# NVME.net
KiCad netlist of a schematic drawn in Altium Designer
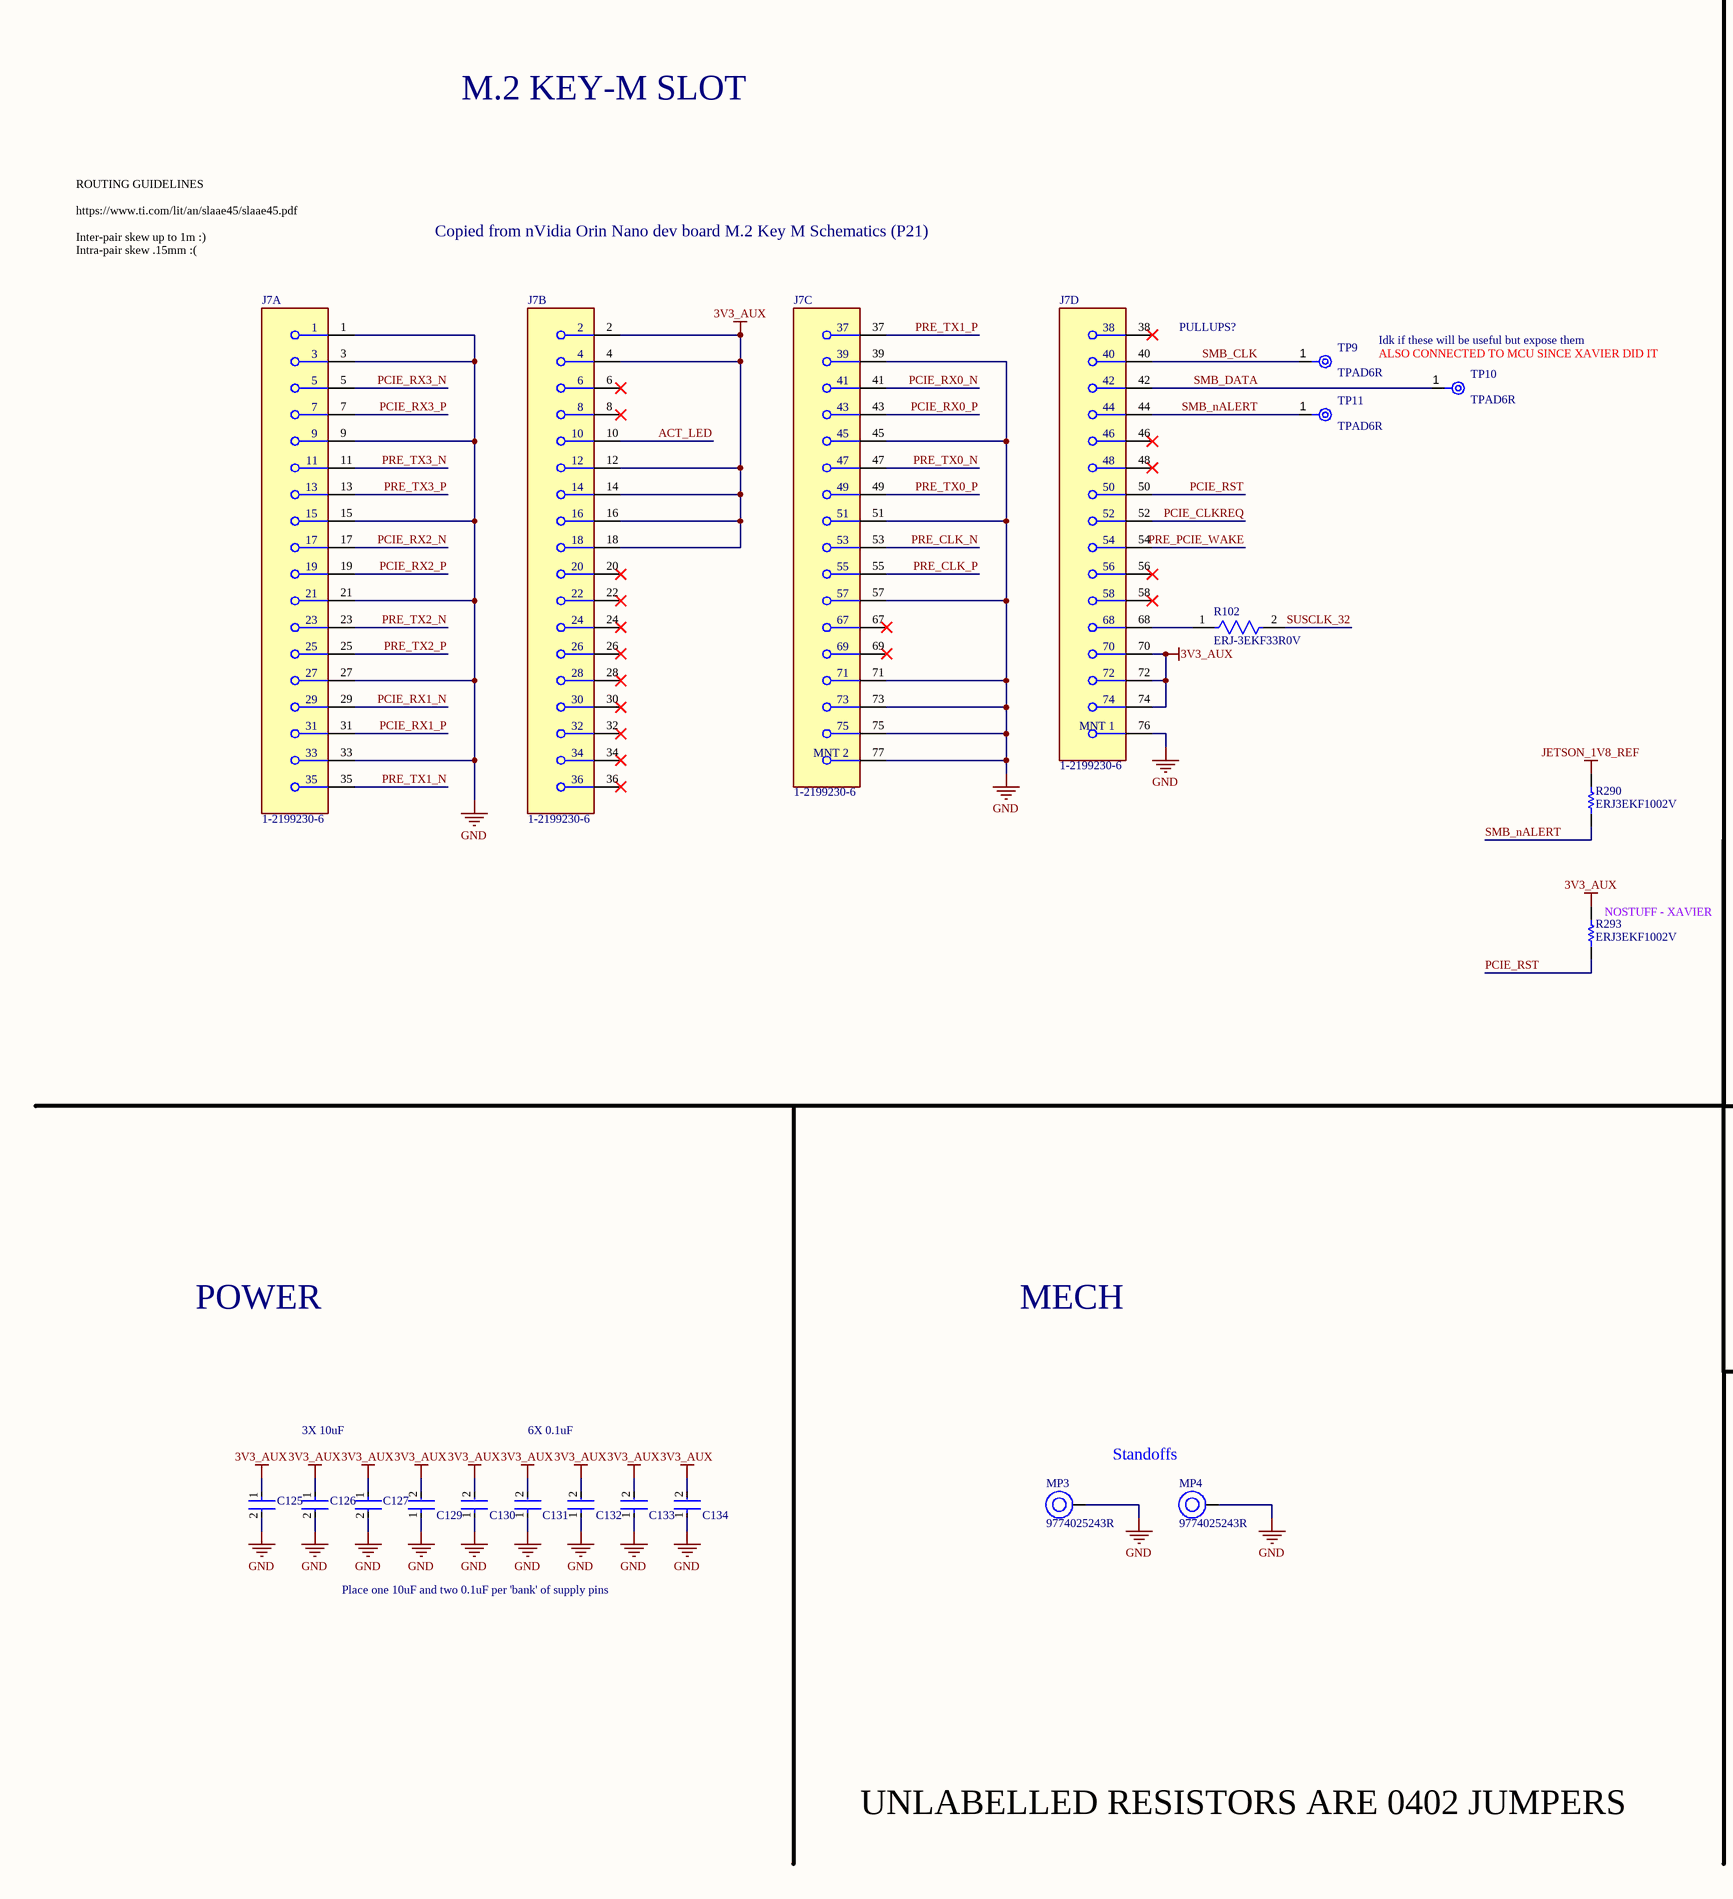
[diagram p0: NVME.SchDoc, left]
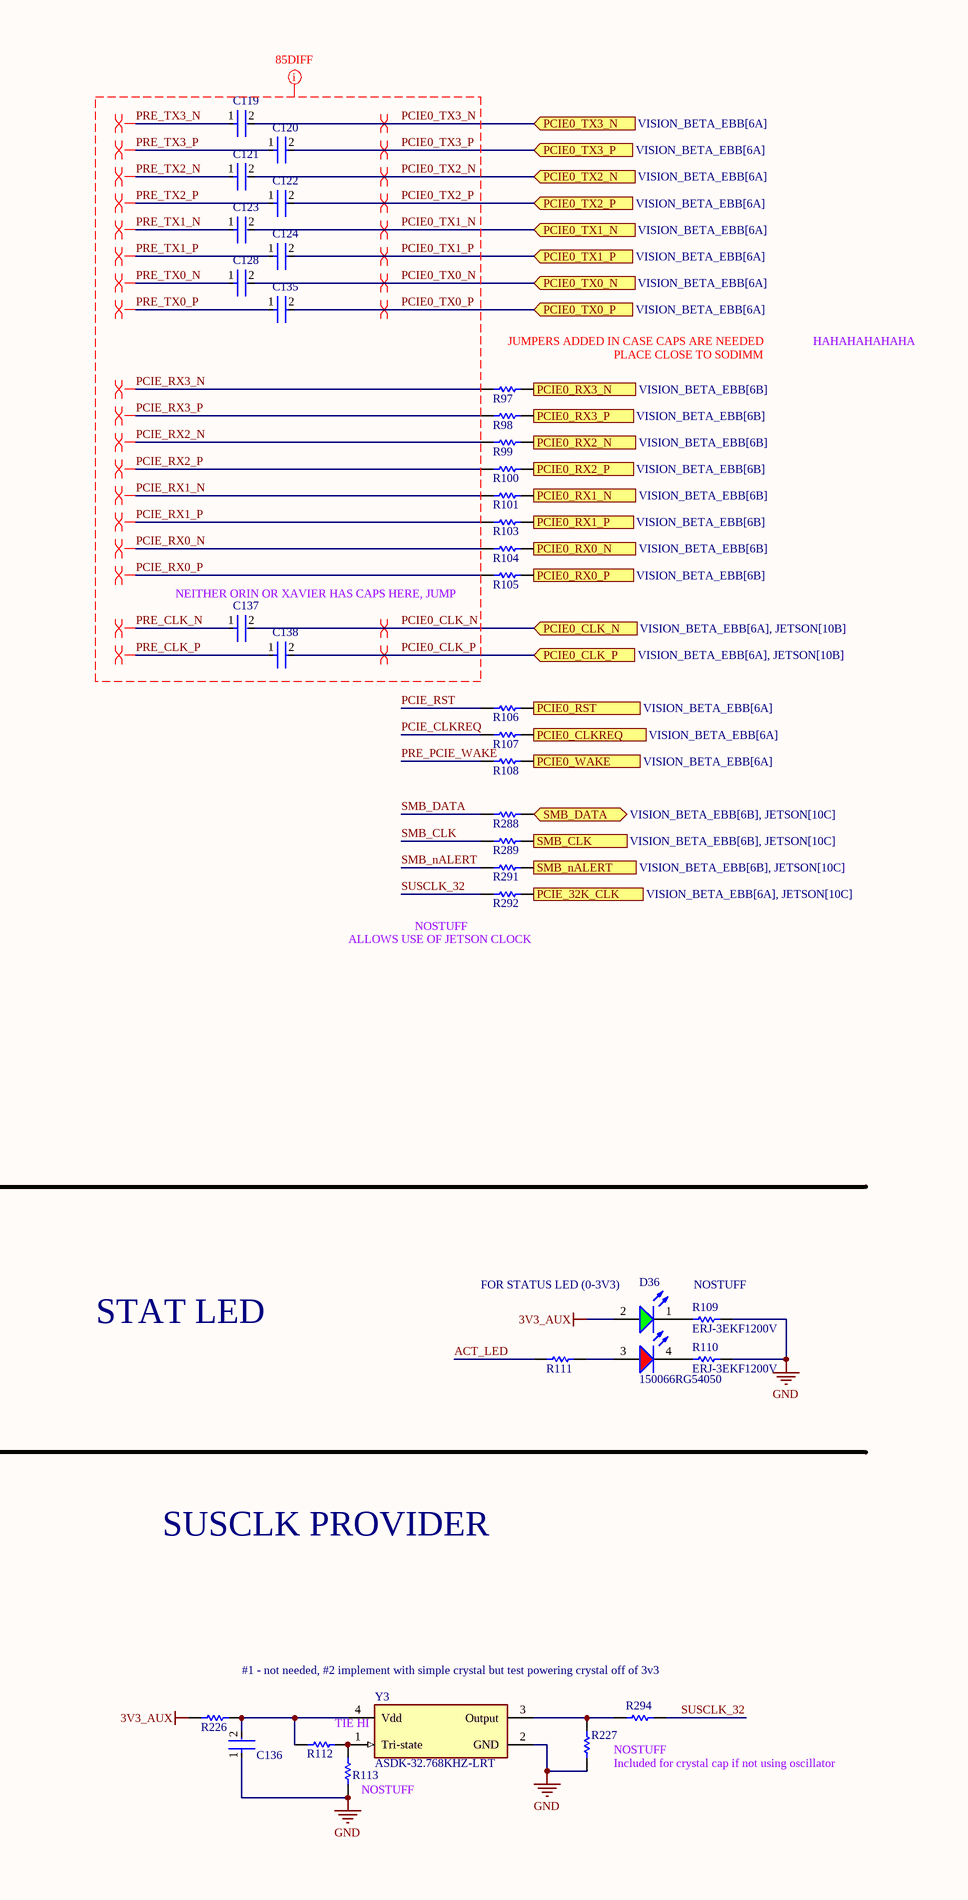
[diagram p1: NVME.SchDoc, right]

(export (version "E")
  (design (tool "Eeschema 10.0.6"))
  (components
    (comp (ref "C119")
      (value "C1005X7R1A224K050BB")
      (footprint "FP-C1005-050-0_05-IPC_C")
      (description "Multilayer Ceramic Capacitors 220nF ±10% 10V X7R SMD 0402")
      (fields (field (name "TOLERANCE") "10%"))
      (libsource (lib "Altium Content Vault") (part "b4654b650e69147ec39a6b967a45e02"))
    )
    (comp (ref "C120")
      (value "C1005X7R1A224K050BB")
      (footprint "FP-C1005-050-0_05-IPC_C")
      (description "Multilayer Ceramic Capacitors 220nF ±10% 10V X7R SMD 0402")
      (fields (field (name "TOLERANCE") "10%"))
      (libsource (lib "Altium Content Vault") (part "b4654b650e69147ec39a6b967a45e02"))
    )
    (comp (ref "C121")
      (value "C1005X7R1A224K050BB")
      (footprint "FP-C1005-050-0_05-IPC_C")
      (description "Multilayer Ceramic Capacitors 220nF ±10% 10V X7R SMD 0402")
      (fields (field (name "TOLERANCE") "10%"))
      (libsource (lib "Altium Content Vault") (part "b4654b650e69147ec39a6b967a45e02"))
    )
    (comp (ref "C122")
      (value "C1005X7R1A224K050BB")
      (footprint "FP-C1005-050-0_05-IPC_C")
      (description "Multilayer Ceramic Capacitors 220nF ±10% 10V X7R SMD 0402")
      (fields (field (name "TOLERANCE") "10%"))
      (libsource (lib "Altium Content Vault") (part "b4654b650e69147ec39a6b967a45e02"))
    )
    (comp (ref "C123")
      (value "C1005X7R1A224K050BB")
      (footprint "FP-C1005-050-0_05-IPC_C")
      (description "Multilayer Ceramic Capacitors 220nF ±10% 10V X7R SMD 0402")
      (fields (field (name "TOLERANCE") "10%"))
      (libsource (lib "Altium Content Vault") (part "b4654b650e69147ec39a6b967a45e02"))
    )
    (comp (ref "C124")
      (value "C1005X7R1A224K050BB")
      (footprint "FP-C1005-050-0_05-IPC_C")
      (description "Multilayer Ceramic Capacitors 220nF ±10% 10V X7R SMD 0402")
      (fields (field (name "TOLERANCE") "10%"))
      (libsource (lib "Altium Content Vault") (part "b4654b650e69147ec39a6b967a45e02"))
    )
    (comp (ref "C125")
      (value "GRM188R60J106ME47D")
      (footprint "FP-GRM188-0_1-e0_2_0_55-IPC_A")
      (description "Chip Multilayer Ceramic Capacitors for General Purpose, 0603, 10uF, X5R, 15%, 20%, 6.3V")
      (fields (field (name "VOLTAGE") "6.3V") (field (name "TOLERANCE") "20%"))
      (libsource (lib "Altium Content Vault") (part "02cd4be3c70576c341d710602a673aa"))
    )
    (comp (ref "C126")
      (value "GRM188R60J106ME47D")
      (footprint "FP-GRM188-0_1-e0_2_0_55-IPC_A")
      (description "Chip Multilayer Ceramic Capacitors for General Purpose, 0603, 10uF, X5R, 15%, 20%, 6.3V")
      (fields (field (name "VOLTAGE") "6.3V") (field (name "TOLERANCE") "20%"))
      (libsource (lib "Altium Content Vault") (part "02cd4be3c70576c341d710602a673aa"))
    )
    (comp (ref "C127")
      (value "GRM188R60J106ME47D")
      (footprint "FP-GRM188-0_1-e0_2_0_55-IPC_A")
      (description "Chip Multilayer Ceramic Capacitors for General Purpose, 0603, 10uF, X5R, 15%, 20%, 6.3V")
      (fields (field (name "VOLTAGE") "6.3V") (field (name "TOLERANCE") "20%"))
      (libsource (lib "Altium Content Vault") (part "02cd4be3c70576c341d710602a673aa"))
    )
    (comp (ref "C128")
      (value "C1005X7R1A224K050BB")
      (footprint "FP-C1005-050-0_05-IPC_C")
      (description "Multilayer Ceramic Capacitors 220nF ±10% 10V X7R SMD 0402")
      (fields (field (name "TOLERANCE") "10%"))
      (libsource (lib "Altium Content Vault") (part "b4654b650e69147ec39a6b967a45e02"))
    )
    (comp (ref "C129")
      (value "C1005X7R1H104K050BB")
      (footprint "FP-C1005-050-0_05-IPC_C")
      (description "Multilayer Ceramic Capacitors 100nF ±10% 50V X7R SMD 0402")
      (fields (field (name "VOLTAGE") "50V") (field (name "TOLERANCE") "10%"))
      (libsource (lib "Altium Content Vault") (part "b4654b650e69147ec39a6b967a45e02"))
    )
    (comp (ref "C130")
      (value "C1005X7R1H104K050BB")
      (footprint "FP-C1005-050-0_05-IPC_C")
      (description "Multilayer Ceramic Capacitors 100nF ±10% 50V X7R SMD 0402")
      (fields (field (name "VOLTAGE") "50V") (field (name "TOLERANCE") "10%"))
      (libsource (lib "Altium Content Vault") (part "b4654b650e69147ec39a6b967a45e02"))
    )
    (comp (ref "C131")
      (value "C1005X7R1H104K050BB")
      (footprint "FP-C1005-050-0_05-IPC_C")
      (description "Multilayer Ceramic Capacitors 100nF ±10% 50V X7R SMD 0402")
      (fields (field (name "VOLTAGE") "50V") (field (name "TOLERANCE") "10%"))
      (libsource (lib "Altium Content Vault") (part "b4654b650e69147ec39a6b967a45e02"))
    )
    (comp (ref "C132")
      (value "C1005X7R1H104K050BB")
      (footprint "FP-C1005-050-0_05-IPC_C")
      (description "Multilayer Ceramic Capacitors 100nF ±10% 50V X7R SMD 0402")
      (fields (field (name "VOLTAGE") "50V") (field (name "TOLERANCE") "10%"))
      (libsource (lib "Altium Content Vault") (part "b4654b650e69147ec39a6b967a45e02"))
    )
    (comp (ref "C133")
      (value "C1005X7R1H104K050BB")
      (footprint "FP-C1005-050-0_05-IPC_C")
      (description "Multilayer Ceramic Capacitors 100nF ±10% 50V X7R SMD 0402")
      (fields (field (name "VOLTAGE") "50V") (field (name "TOLERANCE") "10%"))
      (libsource (lib "Altium Content Vault") (part "b4654b650e69147ec39a6b967a45e02"))
    )
    (comp (ref "C134")
      (value "C1005X7R1H104K050BB")
      (footprint "FP-C1005-050-0_05-IPC_C")
      (description "Multilayer Ceramic Capacitors 100nF ±10% 50V X7R SMD 0402")
      (fields (field (name "VOLTAGE") "50V") (field (name "TOLERANCE") "10%"))
      (libsource (lib "Altium Content Vault") (part "b4654b650e69147ec39a6b967a45e02"))
    )
    (comp (ref "C135")
      (value "C1005X7R1A224K050BB")
      (footprint "FP-C1005-050-0_05-IPC_C")
      (description "Multilayer Ceramic Capacitors 220nF ±10% 10V X7R SMD 0402")
      (fields (field (name "TOLERANCE") "10%"))
      (libsource (lib "Altium Content Vault") (part "b4654b650e69147ec39a6b967a45e02"))
    )
    (comp (ref "C136")
      (value "C1005X7R1H104K050BB")
      (footprint "FP-C1005-050-0_05-IPC_C")
      (description "Multilayer Ceramic Capacitors 100nF ±10% 50V X7R SMD 0402")
      (fields (field (name "VOLTAGE") "50V") (field (name "TOLERANCE") "10%"))
      (libsource (lib "Altium Content Vault") (part "b4654b650e69147ec39a6b967a45e02"))
    )
    (comp (ref "C137")
      (value "C1005X7R1A224K050BB")
      (footprint "FP-C1005-050-0_05-IPC_C")
      (description "Multilayer Ceramic Capacitors 220nF ±10% 10V X7R SMD 0402")
      (fields (field (name "TOLERANCE") "10%"))
      (libsource (lib "Altium Content Vault") (part "b4654b650e69147ec39a6b967a45e02"))
    )
    (comp (ref "C138")
      (value "C1005X7R1A224K050BB")
      (footprint "FP-C1005-050-0_05-IPC_C")
      (description "Multilayer Ceramic Capacitors 220nF ±10% 10V X7R SMD 0402")
      (fields (field (name "TOLERANCE") "10%"))
      (libsource (lib "Altium Content Vault") (part "b4654b650e69147ec39a6b967a45e02"))
    )
    (comp (ref "D36")
      (value "150066RG54050")
      (footprint "WL-SBCD_0606")
      (description "Led, Red/Grn, 180Mcd/230Mcd, 624Nm/525Nm Rohs Compliant: Yes")
      (fields (field (name "SOURCE") "rgled.SchLib"))
      (libsource (lib "Space Concordia") (part "CMP-004-00034-2"))
    )
    (comp (ref "J7")
      (value "1-2199230-6")
      (footprint "FP-1-2199230-6-MFG")
      (description "CONN EDGE DUAL FMALE 67POS 0.020")
      (fields
        (field (name "MANUFACTURER") "TE")
        (field (name "OCTOPART") "https://octopart.com/1-2199230-6-te+connectivity-34969376")
      )
      (libsource (lib "Altium Content Vault") (part "bdc5cd39fb5e3adfc3cf7d042564072"))
    )
    (comp (ref "MP3")
      (value "9774025243R")
      (footprint "9774025243")
      (description "9774025243R Spacer Material: Steel, Tin-Plated Mounting: SMT Series: WA-SMST Thread D: M2")
      (libsource (lib "Altium Content Vault") (part "Spacer"))
    )
    (comp (ref "MP4")
      (value "9774025243R")
      (footprint "9774025243")
      (description "9774025243R Spacer Material: Steel, Tin-Plated Mounting: SMT Series: WA-SMST Thread D: M2")
      (libsource (lib "Altium Content Vault") (part "Spacer"))
    )
    (comp (ref "R97")
      (value "0402 JUMPER")
      (footprint "RESC1005X40X25ML05T05")
      (description "READ THE NAME")
      (libsource (lib "Space Concordia") (part "CMP-009-00206-2"))
    )
    (comp (ref "R98")
      (value "0402 JUMPER")
      (footprint "RESC1005X40X25ML05T05")
      (description "READ THE NAME")
      (libsource (lib "Space Concordia") (part "CMP-009-00206-2"))
    )
    (comp (ref "R99")
      (value "0402 JUMPER")
      (footprint "RESC1005X40X25ML05T05")
      (description "READ THE NAME")
      (libsource (lib "Space Concordia") (part "CMP-009-00206-2"))
    )
    (comp (ref "R100")
      (value "0402 JUMPER")
      (footprint "RESC1005X40X25ML05T05")
      (description "READ THE NAME")
      (libsource (lib "Space Concordia") (part "CMP-009-00206-2"))
    )
    (comp (ref "R101")
      (value "0402 JUMPER")
      (footprint "RESC1005X40X25ML05T05")
      (description "READ THE NAME")
      (libsource (lib "Space Concordia") (part "CMP-009-00206-2"))
    )
    (comp (ref "R102")
      (value "ERJ-3EKF33R0V")
      (footprint "FP-ERJ3EK-MFG")
      (description "RES SMD 33 OHM 1% 1/10W 0603")
      (fields (field (name "TOLERANCE") "1%"))
      (libsource (lib "Altium Content Vault") (part "1029c3af85768c4190bb7ad29bc67b5"))
    )
    (comp (ref "R103")
      (value "0402 JUMPER")
      (footprint "RESC1005X40X25ML05T05")
      (description "READ THE NAME")
      (libsource (lib "Space Concordia") (part "CMP-009-00206-2"))
    )
    (comp (ref "R104")
      (value "0402 JUMPER")
      (footprint "RESC1005X40X25ML05T05")
      (description "READ THE NAME")
      (libsource (lib "Space Concordia") (part "CMP-009-00206-2"))
    )
    (comp (ref "R105")
      (value "0402 JUMPER")
      (footprint "RESC1005X40X25ML05T05")
      (description "READ THE NAME")
      (libsource (lib "Space Concordia") (part "CMP-009-00206-2"))
    )
    (comp (ref "R106")
      (value "0402 JUMPER")
      (footprint "RESC1005X40X25ML05T05")
      (description "READ THE NAME")
      (libsource (lib "Space Concordia") (part "CMP-009-00206-2"))
    )
    (comp (ref "R107")
      (value "0402 JUMPER")
      (footprint "RESC1005X40X25ML05T05")
      (description "READ THE NAME")
      (libsource (lib "Space Concordia") (part "CMP-009-00206-2"))
    )
    (comp (ref "R108")
      (value "0402 JUMPER")
      (footprint "RESC1005X40X25ML05T05")
      (description "READ THE NAME")
      (libsource (lib "Space Concordia") (part "CMP-009-00206-2"))
    )
    (comp (ref "R109")
      (value "ERJ-3EKF1200V")
      (footprint "RESC1609X55X30ML15T15")
      (description "Chip Resistor, 120 Ohm, +/- 1%, 0.1 W, -55 to 155 degC, 0603 (1608 Metric), RoHS, Tape and Reel")
      (fields (field (name "TOLERANCE") "1%") (field (name "MANUFACTURER") "Panasonic"))
      (libsource (lib "Altium Content Vault") (part "RES-2"))
    )
    (comp (ref "R110")
      (value "ERJ-3EKF1200V")
      (footprint "RESC1609X55X30ML15T15")
      (description "Chip Resistor, 120 Ohm, +/- 1%, 0.1 W, -55 to 155 degC, 0603 (1608 Metric), RoHS, Tape and Reel")
      (fields (field (name "TOLERANCE") "1%") (field (name "MANUFACTURER") "Panasonic"))
      (libsource (lib "Altium Content Vault") (part "RES-2"))
    )
    (comp (ref "R111")
      (value "0402 JUMPER")
      (footprint "RESC1005X40X25ML05T05")
      (description "READ THE NAME")
      (libsource (lib "Space Concordia") (part "CMP-009-00206-2"))
    )
    (comp (ref "R112")
      (value "0402 JUMPER")
      (footprint "RESC1005X40X25ML05T05")
      (description "READ THE NAME")
      (libsource (lib "Space Concordia") (part "CMP-009-00206-2"))
    )
    (comp (ref "R113")
      (value "0402 JUMPER")
      (footprint "RESC1005X40X25ML05T05")
      (description "READ THE NAME")
      (libsource (lib "Space Concordia") (part "CMP-009-00206-2"))
    )
    (comp (ref "R226")
      (value "0402 JUMPER")
      (footprint "RESC1005X40X25ML05T05")
      (description "READ THE NAME")
      (libsource (lib "Space Concordia") (part "CMP-009-00206-2"))
    )
    (comp (ref "R227")
      (value "0402 JUMPER")
      (footprint "RESC1005X40X25ML05T05")
      (description "READ THE NAME")
      (libsource (lib "Space Concordia") (part "CMP-009-00206-2"))
    )
    (comp (ref "R288")
      (value "0402 JUMPER")
      (footprint "RESC1005X40X25ML05T05")
      (description "READ THE NAME")
      (libsource (lib "Space Concordia") (part "CMP-009-00206-2"))
    )
    (comp (ref "R289")
      (value "0402 JUMPER")
      (footprint "RESC1005X40X25ML05T05")
      (description "READ THE NAME")
      (libsource (lib "Space Concordia") (part "CMP-009-00206-2"))
    )
    (comp (ref "R290")
      (value "ERJ3EKF1002V")
      (footprint "RESC1609X55X30LL15T15")
      (description "Chip Resistor, 10 KOhm, +/- 1%, 0.1 W, -55 to 155 degC, 0603 (1608 Metric), RoHS, Tape and Reel")
      (fields (field (name "TOLERANCE") "1%") (field (name "MANUFACTURER") "Panasonic"))
      (libsource (lib "Altium Content Vault") (part "RES-2"))
    )
    (comp (ref "R291")
      (value "0402 JUMPER")
      (footprint "RESC1005X40X25ML05T05")
      (description "READ THE NAME")
      (libsource (lib "Space Concordia") (part "CMP-009-00206-2"))
    )
    (comp (ref "R292")
      (value "0402 JUMPER")
      (footprint "RESC1005X40X25ML05T05")
      (description "READ THE NAME")
      (libsource (lib "Space Concordia") (part "CMP-009-00206-2"))
    )
    (comp (ref "R293")
      (value "ERJ3EKF1002V")
      (footprint "RESC1609X55X30LL15T15")
      (description "Chip Resistor, 10 KOhm, +/- 1%, 0.1 W, -55 to 155 degC, 0603 (1608 Metric), RoHS, Tape and Reel")
      (fields (field (name "TOLERANCE") "1%") (field (name "MANUFACTURER") "Panasonic"))
      (libsource (lib "Altium Content Vault") (part "RES-2"))
    )
    (comp (ref "R294")
      (value "0402 JUMPER")
      (footprint "RESC1005X40X25ML05T05")
      (description "READ THE NAME")
      (libsource (lib "Space Concordia") (part "CMP-009-00206-2"))
    )
    (comp (ref "TP9")
      (value "TPAD6R")
      (footprint "New footprint 1")
      (description "Test Point .6mm")
      (libsource (lib "Space Concordia") (part "TP"))
    )
    (comp (ref "TP10")
      (value "TPAD6R")
      (footprint "New footprint 1")
      (description "Test Point .6mm")
      (libsource (lib "Space Concordia") (part "TP"))
    )
    (comp (ref "TP11")
      (value "TPAD6R")
      (footprint "New footprint 1")
      (description "Test Point .6mm")
      (libsource (lib "Space Concordia") (part "TP"))
    )
    (comp (ref "Y3")
      (value "ASDK-32.768KHZ-LRT")
      (footprint "FP-ASDK-MFG")
      (description "XTAL OSC XO 32.7680KHZ CMOS SMD")
      (libsource (lib "Altium Content Vault") (part "a7425352bb6ebc83bfd0f12a23808e7"))
    )
  )
  (nets
    (net (code "1") (name "/ACT_LED") (class "Default")
      (node (ref "J7") (pin "10") (pinfunction "10_10") (pintype "passive"))
      (node (ref "R111") (pin "1") (pinfunction "1_1") (pintype "passive"))
    )
    (net (code "2") (name "/PCIE0_CLKREQ") (class "Default")
      (node (ref "R107") (pin "2") (pinfunction "2_2") (pintype "passive"))
    )
    (net (code "3") (name "/PCIE0_CLK_N") (class "Default")
      (node (ref "C137") (pin "2") (pinfunction "2_2") (pintype "passive"))
    )
    (net (code "4") (name "/PCIE0_CLK_P") (class "Default")
      (node (ref "C138") (pin "2") (pinfunction "2_2") (pintype "passive"))
    )
    (net (code "5") (name "/PCIE0_RST") (class "Default")
      (node (ref "R106") (pin "2") (pinfunction "2_2") (pintype "passive"))
    )
    (net (code "6") (name "/PCIE0_RX0_N") (class "Default")
      (node (ref "R104") (pin "2") (pinfunction "2_2") (pintype "passive"))
    )
    (net (code "7") (name "/PCIE0_RX0_P") (class "Default")
      (node (ref "R105") (pin "2") (pinfunction "2_2") (pintype "passive"))
    )
    (net (code "8") (name "/PCIE0_RX1_N") (class "Default")
      (node (ref "R101") (pin "2") (pinfunction "2_2") (pintype "passive"))
    )
    (net (code "9") (name "/PCIE0_RX1_P") (class "Default")
      (node (ref "R103") (pin "2") (pinfunction "2_2") (pintype "passive"))
    )
    (net (code "10") (name "/PCIE0_RX2_N") (class "Default")
      (node (ref "R99") (pin "2") (pinfunction "2_2") (pintype "passive"))
    )
    (net (code "11") (name "/PCIE0_RX2_P") (class "Default")
      (node (ref "R100") (pin "2") (pinfunction "2_2") (pintype "passive"))
    )
    (net (code "12") (name "/PCIE0_RX3_N") (class "Default")
      (node (ref "R97") (pin "2") (pinfunction "2_2") (pintype "passive"))
    )
    (net (code "13") (name "/PCIE0_RX3_P") (class "Default")
      (node (ref "R98") (pin "2") (pinfunction "2_2") (pintype "passive"))
    )
    (net (code "14") (name "/PCIE0_TX0_N") (class "Default")
      (node (ref "C128") (pin "2") (pinfunction "2_2") (pintype "passive"))
    )
    (net (code "15") (name "/PCIE0_TX0_P") (class "Default")
      (node (ref "C135") (pin "2") (pinfunction "2_2") (pintype "passive"))
    )
    (net (code "16") (name "/PCIE0_TX1_N") (class "Default")
      (node (ref "C123") (pin "2") (pinfunction "2_2") (pintype "passive"))
    )
    (net (code "17") (name "/PCIE0_TX1_P") (class "Default")
      (node (ref "C124") (pin "2") (pinfunction "2_2") (pintype "passive"))
    )
    (net (code "18") (name "/PCIE0_TX2_N") (class "Default")
      (node (ref "C121") (pin "2") (pinfunction "2_2") (pintype "passive"))
    )
    (net (code "19") (name "/PCIE0_TX2_P") (class "Default")
      (node (ref "C122") (pin "2") (pinfunction "2_2") (pintype "passive"))
    )
    (net (code "20") (name "/PCIE0_TX3_N") (class "Default")
      (node (ref "C119") (pin "2") (pinfunction "2_2") (pintype "passive"))
    )
    (net (code "21") (name "/PCIE0_TX3_P") (class "Default")
      (node (ref "C120") (pin "2") (pinfunction "2_2") (pintype "passive"))
    )
    (net (code "22") (name "/PCIE0_WAKE") (class "Default")
      (node (ref "R108") (pin "2") (pinfunction "2_2") (pintype "passive"))
    )
    (net (code "23") (name "/PCIE_32K_CLK") (class "Default")
      (node (ref "R292") (pin "2") (pinfunction "2_2") (pintype "passive"))
    )
    (net (code "24") (name "/PCIE_CLKREQ") (class "Default")
      (node (ref "J7") (pin "52") (pinfunction "52_52") (pintype "passive"))
      (node (ref "R107") (pin "1") (pinfunction "1_1") (pintype "passive"))
    )
    (net (code "25") (name "/PCIE_RST") (class "Default")
      (node (ref "J7") (pin "50") (pinfunction "50_50") (pintype "passive"))
      (node (ref "R106") (pin "1") (pinfunction "1_1") (pintype "passive"))
      (node (ref "R293") (pin "1") (pinfunction "1_1") (pintype "passive"))
    )
    (net (code "26") (name "/PCIE_RX0_N") (class "Default")
      (node (ref "J7") (pin "41") (pinfunction "41_41") (pintype "passive"))
      (node (ref "R104") (pin "1") (pinfunction "1_1") (pintype "passive"))
    )
    (net (code "27") (name "/PCIE_RX0_P") (class "Default")
      (node (ref "J7") (pin "43") (pinfunction "43_43") (pintype "passive"))
      (node (ref "R105") (pin "1") (pinfunction "1_1") (pintype "passive"))
    )
    (net (code "28") (name "/PCIE_RX1_N") (class "Default")
      (node (ref "J7") (pin "29") (pinfunction "29_29") (pintype "passive"))
      (node (ref "R101") (pin "1") (pinfunction "1_1") (pintype "passive"))
    )
    (net (code "29") (name "/PCIE_RX1_P") (class "Default")
      (node (ref "J7") (pin "31") (pinfunction "31_31") (pintype "passive"))
      (node (ref "R103") (pin "1") (pinfunction "1_1") (pintype "passive"))
    )
    (net (code "30") (name "/PCIE_RX2_N") (class "Default")
      (node (ref "J7") (pin "17") (pinfunction "17_17") (pintype "passive"))
      (node (ref "R99") (pin "1") (pinfunction "1_1") (pintype "passive"))
    )
    (net (code "31") (name "/PCIE_RX2_P") (class "Default")
      (node (ref "J7") (pin "19") (pinfunction "19_19") (pintype "passive"))
      (node (ref "R100") (pin "1") (pinfunction "1_1") (pintype "passive"))
    )
    (net (code "32") (name "/PCIE_RX3_N") (class "Default")
      (node (ref "J7") (pin "5") (pinfunction "5_5") (pintype "passive"))
      (node (ref "R97") (pin "1") (pinfunction "1_1") (pintype "passive"))
    )
    (net (code "33") (name "/PCIE_RX3_P") (class "Default")
      (node (ref "J7") (pin "7") (pinfunction "7_7") (pintype "passive"))
      (node (ref "R98") (pin "1") (pinfunction "1_1") (pintype "passive"))
    )
    (net (code "34") (name "/PRE_CLK_N") (class "Default")
      (node (ref "C137") (pin "1") (pinfunction "1_1") (pintype "passive"))
      (node (ref "J7") (pin "53") (pinfunction "53_53") (pintype "passive"))
    )
    (net (code "35") (name "/PRE_CLK_P") (class "Default")
      (node (ref "C138") (pin "1") (pinfunction "1_1") (pintype "passive"))
      (node (ref "J7") (pin "55") (pinfunction "55_55") (pintype "passive"))
    )
    (net (code "36") (name "/PRE_PCIE_WAKE") (class "Default")
      (node (ref "J7") (pin "54") (pinfunction "54_54") (pintype "passive"))
      (node (ref "R108") (pin "1") (pinfunction "1_1") (pintype "passive"))
    )
    (net (code "37") (name "/PRE_TX0_N") (class "Default")
      (node (ref "C128") (pin "1") (pinfunction "1_1") (pintype "passive"))
      (node (ref "J7") (pin "47") (pinfunction "47_47") (pintype "passive"))
    )
    (net (code "38") (name "/PRE_TX0_P") (class "Default")
      (node (ref "C135") (pin "1") (pinfunction "1_1") (pintype "passive"))
      (node (ref "J7") (pin "49") (pinfunction "49_49") (pintype "passive"))
    )
    (net (code "39") (name "/PRE_TX1_N") (class "Default")
      (node (ref "C123") (pin "1") (pinfunction "1_1") (pintype "passive"))
      (node (ref "J7") (pin "35") (pinfunction "35_35") (pintype "passive"))
    )
    (net (code "40") (name "/PRE_TX1_P") (class "Default")
      (node (ref "C124") (pin "1") (pinfunction "1_1") (pintype "passive"))
      (node (ref "J7") (pin "37") (pinfunction "37_37") (pintype "passive"))
    )
    (net (code "41") (name "/PRE_TX2_N") (class "Default")
      (node (ref "C121") (pin "1") (pinfunction "1_1") (pintype "passive"))
      (node (ref "J7") (pin "23") (pinfunction "23_23") (pintype "passive"))
    )
    (net (code "42") (name "/PRE_TX2_P") (class "Default")
      (node (ref "C122") (pin "1") (pinfunction "1_1") (pintype "passive"))
      (node (ref "J7") (pin "25") (pinfunction "25_25") (pintype "passive"))
    )
    (net (code "43") (name "/PRE_TX3_N") (class "Default")
      (node (ref "C119") (pin "1") (pinfunction "1_1") (pintype "passive"))
      (node (ref "J7") (pin "11") (pinfunction "11_11") (pintype "passive"))
    )
    (net (code "44") (name "/PRE_TX3_P") (class "Default")
      (node (ref "C120") (pin "1") (pinfunction "1_1") (pintype "passive"))
      (node (ref "J7") (pin "13") (pinfunction "13_13") (pintype "passive"))
    )
    (net (code "45") (name "/SMB_CLK") (class "Default")
      (node (ref "J7") (pin "40") (pinfunction "40_40") (pintype "passive"))
      (node (ref "R289") (pin "1") (pinfunction "1_1") (pintype "passive"))
      (node (ref "TP9") (pin "1") (pinfunction "TP_1") (pintype "passive"))
    )
    (net (code "46") (name "/SMB_DATA") (class "Default")
      (node (ref "J7") (pin "42") (pinfunction "42_42") (pintype "passive"))
      (node (ref "R288") (pin "1") (pinfunction "1_1") (pintype "passive"))
      (node (ref "TP10") (pin "1") (pinfunction "TP_1") (pintype "passive"))
    )
    (net (code "47") (name "/SMB_nALERT") (class "Default")
      (node (ref "J7") (pin "44") (pinfunction "44_44") (pintype "passive"))
      (node (ref "R290") (pin "1") (pinfunction "1_1") (pintype "passive"))
      (node (ref "R291") (pin "1") (pinfunction "1_1") (pintype "passive"))
      (node (ref "TP11") (pin "1") (pinfunction "TP_1") (pintype "passive"))
    )
    (net (code "48") (name "/SUSCLK_32") (class "Default")
      (node (ref "R102") (pin "2") (pinfunction "2_2") (pintype "passive"))
      (node (ref "R292") (pin "1") (pinfunction "1_1") (pintype "passive"))
      (node (ref "R294") (pin "1") (pinfunction "1_1") (pintype "passive"))
    )
    (net (code "49") (name "3V3_AUX") (class "Default")
      (node (ref "C125") (pin "1") (pinfunction "1_1") (pintype "passive"))
      (node (ref "C126") (pin "1") (pinfunction "1_1") (pintype "passive"))
      (node (ref "C127") (pin "1") (pinfunction "1_1") (pintype "passive"))
      (node (ref "C129") (pin "2") (pinfunction "2_2") (pintype "passive"))
      (node (ref "C130") (pin "2") (pinfunction "2_2") (pintype "passive"))
      (node (ref "C131") (pin "2") (pinfunction "2_2") (pintype "passive"))
      (node (ref "C132") (pin "2") (pinfunction "2_2") (pintype "passive"))
      (node (ref "C133") (pin "2") (pinfunction "2_2") (pintype "passive"))
      (node (ref "C134") (pin "2") (pinfunction "2_2") (pintype "passive"))
      (node (ref "D36") (pin "2") (pinfunction "A_2") (pintype "passive"))
      (node (ref "J7") (pin "12") (pinfunction "12_12") (pintype "passive"))
      (node (ref "J7") (pin "14") (pinfunction "14_14") (pintype "passive"))
      (node (ref "J7") (pin "16") (pinfunction "16_16") (pintype "passive"))
      (node (ref "J7") (pin "18") (pinfunction "18_18") (pintype "passive"))
      (node (ref "J7") (pin "2") (pinfunction "2_2") (pintype "passive"))
      (node (ref "J7") (pin "4") (pinfunction "4_4") (pintype "passive"))
      (node (ref "J7") (pin "70") (pinfunction "70_70") (pintype "passive"))
      (node (ref "J7") (pin "72") (pinfunction "72_72") (pintype "passive"))
      (node (ref "J7") (pin "74") (pinfunction "74_74") (pintype "passive"))
      (node (ref "R226") (pin "1") (pinfunction "1_1") (pintype "passive"))
      (node (ref "R293") (pin "2") (pinfunction "2_2") (pintype "passive"))
    )
    (net (code "50") (name "GND") (class "Default")
      (node (ref "C125") (pin "2") (pinfunction "2_2") (pintype "passive"))
      (node (ref "C126") (pin "2") (pinfunction "2_2") (pintype "passive"))
      (node (ref "C127") (pin "2") (pinfunction "2_2") (pintype "passive"))
      (node (ref "C129") (pin "1") (pinfunction "1_1") (pintype "passive"))
      (node (ref "C130") (pin "1") (pinfunction "1_1") (pintype "passive"))
      (node (ref "C131") (pin "1") (pinfunction "1_1") (pintype "passive"))
      (node (ref "C132") (pin "1") (pinfunction "1_1") (pintype "passive"))
      (node (ref "C133") (pin "1") (pinfunction "1_1") (pintype "passive"))
      (node (ref "C134") (pin "1") (pinfunction "1_1") (pintype "passive"))
      (node (ref "C136") (pin "1") (pinfunction "1_1") (pintype "passive"))
      (node (ref "J7") (pin "1") (pinfunction "1_1") (pintype "passive"))
      (node (ref "J7") (pin "15") (pinfunction "15_15") (pintype "passive"))
      (node (ref "J7") (pin "21") (pinfunction "21_21") (pintype "passive"))
      (node (ref "J7") (pin "27") (pinfunction "27_27") (pintype "passive"))
      (node (ref "J7") (pin "3") (pinfunction "3_3") (pintype "passive"))
      (node (ref "J7") (pin "33") (pinfunction "33_33") (pintype "passive"))
      (node (ref "J7") (pin "39") (pinfunction "39_39") (pintype "passive"))
      (node (ref "J7") (pin "45") (pinfunction "45_45") (pintype "passive"))
      (node (ref "J7") (pin "51") (pinfunction "51_51") (pintype "passive"))
      (node (ref "J7") (pin "57") (pinfunction "57_57") (pintype "passive"))
      (node (ref "J7") (pin "71") (pinfunction "71_71") (pintype "passive"))
      (node (ref "J7") (pin "73") (pinfunction "73_73") (pintype "passive"))
      (node (ref "J7") (pin "75") (pinfunction "75_75") (pintype "passive"))
      (node (ref "J7") (pin "76") (pinfunction "MNT_1_76") (pintype "passive"))
      (node (ref "J7") (pin "77") (pinfunction "MNT_2_77") (pintype "passive"))
      (node (ref "J7") (pin "9") (pinfunction "9_9") (pintype "passive"))
      (node (ref "MP3") (pin "1") (pinfunction "1_1") (pintype "passive"))
      (node (ref "MP4") (pin "1") (pinfunction "1_1") (pintype "passive"))
      (node (ref "R109") (pin "1") (pinfunction "1_1") (pintype "passive"))
      (node (ref "R110") (pin "1") (pinfunction "1_1") (pintype "passive"))
      (node (ref "R113") (pin "1") (pinfunction "1_1") (pintype "passive"))
      (node (ref "R227") (pin "1") (pinfunction "1_1") (pintype "passive"))
      (node (ref "Y3") (pin "2") (pinfunction "GND_2") (pintype "power_in"))
    )
    (net (code "51") (name "JETSON_1V8_REF") (class "Default")
      (node (ref "R290") (pin "2") (pinfunction "2_2") (pintype "passive"))
    )
    (net (code "52") (name "Net-(D36-A-Pad3)") (class "Default")
      (node (ref "D36") (pin "3") (pinfunction "A_3") (pintype "passive"))
      (node (ref "R111") (pin "2") (pinfunction "2_2") (pintype "passive"))
    )
    (net (code "53") (name "Net-(D36-K-Pad1)") (class "Default")
      (node (ref "D36") (pin "1") (pinfunction "K_1") (pintype "passive"))
      (node (ref "R109") (pin "2") (pinfunction "2_2") (pintype "passive"))
    )
    (net (code "54") (name "Net-(D36-K-Pad4)") (class "Default")
      (node (ref "D36") (pin "4") (pinfunction "K_4") (pintype "passive"))
      (node (ref "R110") (pin "2") (pinfunction "2_2") (pintype "passive"))
    )
    (net (code "55") (name "Net-(J7-Pad68)") (class "Default")
      (node (ref "J7") (pin "68") (pinfunction "68_68") (pintype "passive"))
      (node (ref "R102") (pin "1") (pinfunction "1_1") (pintype "passive"))
    )
    (net (code "56") (name "Net-(Y3-Output)") (class "Default")
      (node (ref "R227") (pin "2") (pinfunction "2_2") (pintype "passive"))
      (node (ref "R294") (pin "2") (pinfunction "2_2") (pintype "passive"))
      (node (ref "Y3") (pin "3") (pinfunction "Output_3") (pintype "tri_state"))
    )
    (net (code "57") (name "Net-(Y3-Tri-state)") (class "Default")
      (node (ref "R112") (pin "2") (pinfunction "2_2") (pintype "passive"))
      (node (ref "R113") (pin "2") (pinfunction "2_2") (pintype "passive"))
      (node (ref "Y3") (pin "1") (pinfunction "Tri-state_1") (pintype "input"))
    )
    (net (code "58") (name "Net-(Y3-Vdd)") (class "Default")
      (node (ref "C136") (pin "2") (pinfunction "2_2") (pintype "passive"))
      (node (ref "R112") (pin "1") (pinfunction "1_1") (pintype "passive"))
      (node (ref "R226") (pin "2") (pinfunction "2_2") (pintype "passive"))
      (node (ref "Y3") (pin "4") (pinfunction "Vdd_4") (pintype "power_in"))
    )
    (net (code "59") (name "unconnected-(J7-Pad6)") (class "Default")
      (node (ref "J7") (pin "6") (pinfunction "6_6") (pintype "passive+no_connect"))
    )
    (net (code "60") (name "unconnected-(J7-Pad8)") (class "Default")
      (node (ref "J7") (pin "8") (pinfunction "8_8") (pintype "passive+no_connect"))
    )
    (net (code "61") (name "unconnected-(J7-Pad20)") (class "Default")
      (node (ref "J7") (pin "20") (pinfunction "20_20") (pintype "passive+no_connect"))
    )
    (net (code "62") (name "unconnected-(J7-Pad22)") (class "Default")
      (node (ref "J7") (pin "22") (pinfunction "22_22") (pintype "passive+no_connect"))
    )
    (net (code "63") (name "unconnected-(J7-Pad24)") (class "Default")
      (node (ref "J7") (pin "24") (pinfunction "24_24") (pintype "passive+no_connect"))
    )
    (net (code "64") (name "unconnected-(J7-Pad26)") (class "Default")
      (node (ref "J7") (pin "26") (pinfunction "26_26") (pintype "passive+no_connect"))
    )
    (net (code "65") (name "unconnected-(J7-Pad28)") (class "Default")
      (node (ref "J7") (pin "28") (pinfunction "28_28") (pintype "passive+no_connect"))
    )
    (net (code "66") (name "unconnected-(J7-Pad30)") (class "Default")
      (node (ref "J7") (pin "30") (pinfunction "30_30") (pintype "passive+no_connect"))
    )
    (net (code "67") (name "unconnected-(J7-Pad32)") (class "Default")
      (node (ref "J7") (pin "32") (pinfunction "32_32") (pintype "passive+no_connect"))
    )
    (net (code "68") (name "unconnected-(J7-Pad34)") (class "Default")
      (node (ref "J7") (pin "34") (pinfunction "34_34") (pintype "passive+no_connect"))
    )
    (net (code "69") (name "unconnected-(J7-Pad36)") (class "Default")
      (node (ref "J7") (pin "36") (pinfunction "36_36") (pintype "passive+no_connect"))
    )
    (net (code "70") (name "unconnected-(J7-Pad38)") (class "Default")
      (node (ref "J7") (pin "38") (pinfunction "38_38") (pintype "passive+no_connect"))
    )
    (net (code "71") (name "unconnected-(J7-Pad46)") (class "Default")
      (node (ref "J7") (pin "46") (pinfunction "46_46") (pintype "passive+no_connect"))
    )
    (net (code "72") (name "unconnected-(J7-Pad48)") (class "Default")
      (node (ref "J7") (pin "48") (pinfunction "48_48") (pintype "passive+no_connect"))
    )
    (net (code "73") (name "unconnected-(J7-Pad56)") (class "Default")
      (node (ref "J7") (pin "56") (pinfunction "56_56") (pintype "passive+no_connect"))
    )
    (net (code "74") (name "unconnected-(J7-Pad58)") (class "Default")
      (node (ref "J7") (pin "58") (pinfunction "58_58") (pintype "passive+no_connect"))
    )
    (net (code "75") (name "unconnected-(J7-Pad67)") (class "Default")
      (node (ref "J7") (pin "67") (pinfunction "67_67") (pintype "passive+no_connect"))
    )
    (net (code "76") (name "unconnected-(J7-Pad69)") (class "Default")
      (node (ref "J7") (pin "69") (pinfunction "69_69") (pintype "passive+no_connect"))
    )
    (net (code "77") (name "unconnected-(R288-Pad2)") (class "Default")
      (node (ref "R288") (pin "2") (pinfunction "2_2") (pintype "passive"))
    )
    (net (code "78") (name "unconnected-(R289-Pad2)") (class "Default")
      (node (ref "R289") (pin "2") (pinfunction "2_2") (pintype "passive"))
    )
    (net (code "79") (name "unconnected-(R291-Pad2)") (class "Default")
      (node (ref "R291") (pin "2") (pinfunction "2_2") (pintype "passive"))
    )
  )
)
